# CC1101-CC1190.net
KiCad netlist of a schematic drawn in Altium Designer
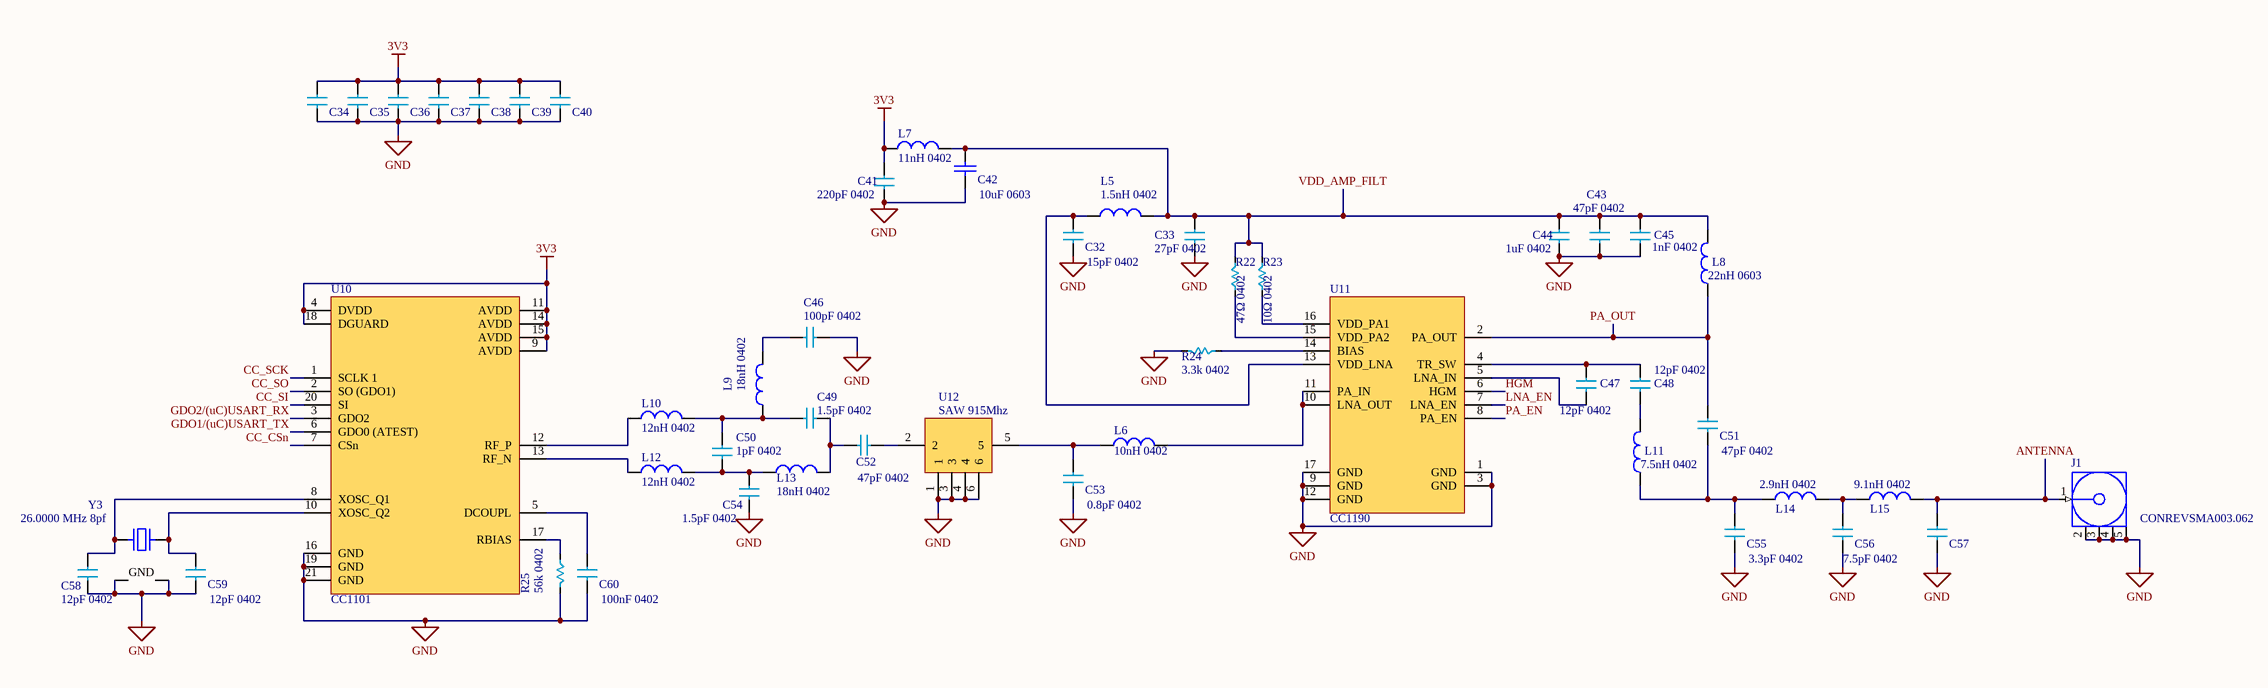
[diagram p0: CC1101-CC1190.SchDoc]

(export (version "E")
  (design (tool "Eeschema 10.0.6"))
  (components
    (comp (ref "C32") (value "15pF 0402") (footprint "C0402") (libsource (lib "RLC") (part "C0402-15pF")))
    (comp (ref "C33") (value "27pF 0402") (footprint "C0402") (libsource (lib "RLC") (part "C0402-27pF")))
    (comp (ref "C34") (value "100nF 0402") (footprint "C0402") (libsource (lib "RLC") (part "C0402-100nF")))
    (comp (ref "C35") (value "100nF 0402") (footprint "C0402") (libsource (lib "RLC") (part "C0402-100nF")))
    (comp (ref "C36") (value "100nF 0402") (footprint "C0402") (libsource (lib "RLC") (part "C0402-100nF")))
    (comp (ref "C37") (value "100nF 0402") (footprint "C0402") (libsource (lib "RLC") (part "C0402-100nF")))
    (comp (ref "C38") (value "100nF 0402") (footprint "C0402") (libsource (lib "RLC") (part "C0402-100nF")))
    (comp (ref "C39") (value "100nF 0402") (footprint "C0402") (libsource (lib "RLC") (part "C0402-100nF")))
    (comp (ref "C40") (value "100nF 0402") (footprint "C0402") (libsource (lib "RLC") (part "C0402-100nF")))
    (comp (ref "C41") (value "220pF 0402") (footprint "C0402") (libsource (lib "RLC") (part "C0402-220pF")))
    (comp (ref "C42") (value "10uF 0603") (footprint "C0603") (libsource (lib "RLC") (part "C-10.0uF-0603")))
    (comp (ref "C43") (value "47pF 0402") (footprint "C0402") (libsource (lib "RLC") (part "C0402-47pF")))
    (comp (ref "C44") (value "1uF 0402") (footprint "C0402") (libsource (lib "RLC") (part "C0402-1uF")))
    (comp (ref "C45") (value "1nF 0402") (footprint "C0402") (libsource (lib "RLC") (part "C0402-1nF")))
    (comp (ref "C46") (value "100pF 0402") (footprint "C0402") (libsource (lib "RLC") (part "C0402-100pF")))
    (comp (ref "C47") (value "12pF 0402") (footprint "C0402") (libsource (lib "RLC") (part "C0402-12pF")))
    (comp (ref "C48") (value "12pF 0402") (footprint "C0402") (libsource (lib "RLC") (part "C0402-12pF")))
    (comp (ref "C49") (value "1.5pF 0402") (footprint "C0402") (libsource (lib "RLC") (part "C0402-1.5pF")))
    (comp (ref "C50") (value "1pF 0402") (footprint "C0402") (libsource (lib "RLC") (part "C0402-1pF")))
    (comp (ref "C51") (value "47pF 0402") (footprint "C0402") (libsource (lib "RLC") (part "C0402-47pF")))
    (comp (ref "C52") (value "47pF 0402") (footprint "C0402") (libsource (lib "RLC") (part "C0402-47pF")))
    (comp (ref "C53") (value "0.8pF 0402") (footprint "C0402") (libsource (lib "RLC") (part "C0402-0.8pF")))
    (comp (ref "C54") (value "1.5pF 0402") (footprint "C0402") (libsource (lib "RLC") (part "C0402-1.5pF")))
    (comp (ref "C55") (value "3.3pF 0402") (footprint "C0402") (libsource (lib "RLC") (part "C0402-3.3pF")))
    (comp (ref "C56") (value "7.5pF 0402") (footprint "C0402") (libsource (lib "RLC") (part "C0402-7.5pF")))
    (comp (ref "C57")
      (value "Placeholder")
      (footprint "C0402")
      (description "Placeholder Cap")
      (libsource (lib "RLC") (part "C0402-?"))
    )
    (comp (ref "C58") (value "12pF 0402") (footprint "C0402") (libsource (lib "RLC") (part "C0402-12pF")))
    (comp (ref "C59") (value "12pF 0402") (footprint "C0402") (libsource (lib "RLC") (part "C0402-12pF")))
    (comp (ref "C60") (value "100nF 0402") (footprint "C0402") (libsource (lib "RLC") (part "C0402-100nF")))
    (comp (ref "J1")
      (value "CONREVSMA003.062")
      (footprint "CON-SMA-EDGE062")
      (description "RP-SMA Female Edge Mount Connector for 0.062\" Thick Board")
      (libsource (lib "robot-cortex") (part "CONREVSMA003.062"))
    )
    (comp (ref "L5") (value "1.5nH 0402") (footprint "L0402") (libsource (lib "RLC") (part "L0402-1.5nH")))
    (comp (ref "L6") (value "10nH 0402") (footprint "L0402") (libsource (lib "RLC") (part "L0402-10nH")))
    (comp (ref "L7") (value "11nH 0402") (footprint "L0402") (libsource (lib "RLC") (part "L0402-11nH")))
    (comp (ref "L8") (value "22nH 0603") (footprint "L0603") (libsource (lib "RLC") (part "L0603-22nH")))
    (comp (ref "L9") (value "18nH 0402") (footprint "L0402") (libsource (lib "RLC") (part "L0402-18nH")))
    (comp (ref "L10") (value "12nH 0402") (footprint "L0402") (libsource (lib "RLC") (part "L0402-12nH")))
    (comp (ref "L11") (value "7.5nH 0402") (footprint "L0402") (libsource (lib "RLC") (part "L0402-7.5nH")))
    (comp (ref "L12") (value "12nH 0402") (footprint "L0402") (libsource (lib "RLC") (part "L0402-12nH")))
    (comp (ref "L13") (value "18nH 0402") (footprint "L0402") (libsource (lib "RLC") (part "L0402-18nH")))
    (comp (ref "L14") (value "2.9nH 0402") (footprint "L0402") (libsource (lib "RLC") (part "L0402-2.9")))
    (comp (ref "L15") (value "9.1nH 0402") (footprint "L0402") (libsource (lib "RLC") (part "L0402-9.1nH")))
    (comp (ref "R22") (value "47Ω 0402") (footprint "R0402") (libsource (lib "RLC") (part "R-47-0402")))
    (comp (ref "R23") (value "10Ω 0402") (footprint "R0402") (libsource (lib "RLC") (part "R-10-0402")))
    (comp (ref "R24") (value "3.3k 0402") (footprint "R0402") (libsource (lib "RLC") (part "R-3.3k-0402")))
    (comp (ref "R25") (value "56k 0402") (footprint "R0402") (libsource (lib "RLC") (part "R-56k-0402")))
    (comp (ref "U10")
      (value "CC1101")
      (footprint "QFN20-TI")
      (description "RF Transceiver IC")
      (libsource (lib "robot-cortex") (part "CC1101"))
    )
    (comp (ref "U11")
      (value "CC1190")
      (footprint "QFN16-TI")
      (description "RF frontend")
      (libsource (lib "robot-cortex") (part "CC1190"))
    )
    (comp (ref "U12")
      (value "SAW 915Mhz")
      (footprint "DCC6C")
      (description "FILTER SAW 915MHZ REMOTE SMD")
      (fields
        (field (name "MANUFACTURER") "TDK EPCOS")
        (field (name "MANUFACTURER PART NUMBER") "B39921B3726U410")
      )
      (libsource (lib "robot-cortex") (part "B39921B3726U410"))
    )
    (comp (ref "Y3")
      (value "26.0000 MHz 8pf")
      (footprint "robot-cortex:NDK NX3225GA")
      (description "Crystal 26MHz 8pF 4-Pin SMD")
      (fields
        (field (name "MANUFACTURER") "NDK")
        (field (name "MANUFACTURER PART NUMBER") "NX3225SA-26.000M-STD-CSR-3")
      )
      (libsource (lib "robot-cortex") (part "NX3225SA-26.000M-STD-CSR-3"))
    )
  )
  (nets
    (net (code "1") (name "/ANTENNA") (class "Default")
      (node (ref "C57") (pin "1") (pinfunction "1_1") (pintype "passive"))
      (node (ref "J1") (pin "1") (pinfunction "Signal_1") (pintype "input"))
      (node (ref "L15") (pin "2") (pinfunction "2_2") (pintype "passive"))
    )
    (net (code "2") (name "/CC_CSn") (class "Default")
      (node (ref "U10") (pin "7") (pinfunction "CSn_7") (pintype "passive"))
    )
    (net (code "3") (name "/CC_SCK") (class "Default")
      (node (ref "U10") (pin "1") (pinfunction "SCLK_1_1") (pintype "passive"))
    )
    (net (code "4") (name "/CC_SI") (class "Default")
      (node (ref "U10") (pin "20") (pinfunction "SI_20") (pintype "passive"))
    )
    (net (code "5") (name "/CC_SO") (class "Default")
      (node (ref "U10") (pin "2") (pinfunction "SO_(GDO1)_2") (pintype "passive"))
    )
    (net (code "6") (name "/GDO1{slash}(uC)USART_TX") (class "Default")
      (node (ref "U10") (pin "6") (pinfunction "GDO0_(ATEST)_6") (pintype "passive"))
    )
    (net (code "7") (name "/GDO2{slash}(uC)USART_RX") (class "Default")
      (node (ref "U10") (pin "3") (pinfunction "GDO2_3") (pintype "passive"))
    )
    (net (code "8") (name "/HGM") (class "Default")
      (node (ref "U11") (pin "6") (pinfunction "HGM_6") (pintype "passive"))
    )
    (net (code "9") (name "/LNA_EN") (class "Default")
      (node (ref "U11") (pin "7") (pinfunction "LNA_EN_7") (pintype "passive"))
    )
    (net (code "10") (name "/PA_EN") (class "Default")
      (node (ref "U11") (pin "8") (pinfunction "PA_EN_8") (pintype "passive"))
    )
    (net (code "11") (name "/PA_OUT") (class "Default")
      (node (ref "C51") (pin "1") (pinfunction "1_1") (pintype "passive"))
      (node (ref "L8") (pin "1") (pinfunction "1_1") (pintype "passive"))
      (node (ref "U11") (pin "2") (pinfunction "PA_OUT_2") (pintype "passive"))
    )
    (net (code "12") (name "/VDD_AMP_FILT") (class "Default")
      (node (ref "C33") (pin "1") (pinfunction "1_1") (pintype "passive"))
      (node (ref "C42") (pin "2") (pinfunction "2_2") (pintype "passive"))
      (node (ref "C43") (pin "1") (pinfunction "1_1") (pintype "passive"))
      (node (ref "C44") (pin "1") (pinfunction "1_1") (pintype "passive"))
      (node (ref "C45") (pin "1") (pinfunction "1_1") (pintype "passive"))
      (node (ref "L5") (pin "2") (pinfunction "2_2") (pintype "passive"))
      (node (ref "L7") (pin "2") (pinfunction "2_2") (pintype "passive"))
      (node (ref "L8") (pin "2") (pinfunction "2_2") (pintype "passive"))
      (node (ref "R22") (pin "1") (pinfunction "1_1") (pintype "passive"))
      (node (ref "R23") (pin "1") (pinfunction "1_1") (pintype "passive"))
    )
    (net (code "13") (name "3V3") (class "Default")
      (node (ref "C34") (pin "2") (pinfunction "2_2") (pintype "passive"))
      (node (ref "C35") (pin "2") (pinfunction "2_2") (pintype "passive"))
      (node (ref "C36") (pin "2") (pinfunction "2_2") (pintype "passive"))
      (node (ref "C37") (pin "2") (pinfunction "2_2") (pintype "passive"))
      (node (ref "C38") (pin "2") (pinfunction "2_2") (pintype "passive"))
      (node (ref "C39") (pin "2") (pinfunction "2_2") (pintype "passive"))
      (node (ref "C40") (pin "2") (pinfunction "2_2") (pintype "passive"))
      (node (ref "C41") (pin "1") (pinfunction "1_1") (pintype "passive"))
      (node (ref "L7") (pin "1") (pinfunction "1_1") (pintype "passive"))
      (node (ref "U10") (pin "11") (pinfunction "AVDD_11") (pintype "passive"))
      (node (ref "U10") (pin "14") (pinfunction "AVDD_14") (pintype "passive"))
      (node (ref "U10") (pin "15") (pinfunction "AVDD_15") (pintype "passive"))
      (node (ref "U10") (pin "18") (pinfunction "DGUARD_18") (pintype "passive"))
      (node (ref "U10") (pin "4") (pinfunction "DVDD_4") (pintype "passive"))
      (node (ref "U10") (pin "9") (pinfunction "AVDD_9") (pintype "passive"))
    )
    (net (code "14") (name "GND") (class "Default")
      (node (ref "C32") (pin "2") (pinfunction "2_2") (pintype "passive"))
      (node (ref "C33") (pin "2") (pinfunction "2_2") (pintype "passive"))
      (node (ref "C34") (pin "1") (pinfunction "1_1") (pintype "passive"))
      (node (ref "C35") (pin "1") (pinfunction "1_1") (pintype "passive"))
      (node (ref "C36") (pin "1") (pinfunction "1_1") (pintype "passive"))
      (node (ref "C37") (pin "1") (pinfunction "1_1") (pintype "passive"))
      (node (ref "C38") (pin "1") (pinfunction "1_1") (pintype "passive"))
      (node (ref "C39") (pin "1") (pinfunction "1_1") (pintype "passive"))
      (node (ref "C40") (pin "1") (pinfunction "1_1") (pintype "passive"))
      (node (ref "C41") (pin "2") (pinfunction "2_2") (pintype "passive"))
      (node (ref "C42") (pin "1") (pinfunction "1_1") (pintype "passive"))
      (node (ref "C43") (pin "2") (pinfunction "2_2") (pintype "passive"))
      (node (ref "C44") (pin "2") (pinfunction "2_2") (pintype "passive"))
      (node (ref "C45") (pin "2") (pinfunction "2_2") (pintype "passive"))
      (node (ref "C46") (pin "1") (pinfunction "1_1") (pintype "passive"))
      (node (ref "C53") (pin "2") (pinfunction "2_2") (pintype "passive"))
      (node (ref "C54") (pin "1") (pinfunction "1_1") (pintype "passive"))
      (node (ref "C55") (pin "2") (pinfunction "2_2") (pintype "passive"))
      (node (ref "C56") (pin "2") (pinfunction "2_2") (pintype "passive"))
      (node (ref "C57") (pin "2") (pinfunction "2_2") (pintype "passive"))
      (node (ref "C58") (pin "1") (pinfunction "1_1") (pintype "passive"))
      (node (ref "C59") (pin "1") (pinfunction "1_1") (pintype "passive"))
      (node (ref "C60") (pin "1") (pinfunction "1_1") (pintype "passive"))
      (node (ref "J1") (pin "2") (pinfunction "GND_2") (pintype "power_in"))
      (node (ref "J1") (pin "3") (pinfunction "GND_3") (pintype "power_in"))
      (node (ref "J1") (pin "4") (pinfunction "GND_4") (pintype "power_in"))
      (node (ref "J1") (pin "5") (pinfunction "GND_5") (pintype "power_in"))
      (node (ref "R24") (pin "1") (pinfunction "1_1") (pintype "passive"))
      (node (ref "R25") (pin "1") (pinfunction "1_1") (pintype "passive"))
      (node (ref "U10") (pin "16") (pinfunction "GND_16") (pintype "passive"))
      (node (ref "U10") (pin "19") (pinfunction "GND_19") (pintype "passive"))
      (node (ref "U10") (pin "21") (pinfunction "GND_21") (pintype "passive"))
      (node (ref "U11") (pin "1") (pinfunction "GND_1") (pintype "passive"))
      (node (ref "U11") (pin "12") (pinfunction "GND_12") (pintype "passive"))
      (node (ref "U11") (pin "17") (pinfunction "GND_17") (pintype "passive"))
      (node (ref "U11") (pin "3") (pinfunction "GND_3") (pintype "passive"))
      (node (ref "U11") (pin "9") (pinfunction "GND_9") (pintype "passive"))
      (node (ref "U12") (pin "1") (pinfunction "1_1") (pintype "passive"))
      (node (ref "U12") (pin "3") (pinfunction "3_3") (pintype "passive"))
      (node (ref "U12") (pin "4") (pinfunction "4_4") (pintype "passive"))
      (node (ref "U12") (pin "6") (pinfunction "6_6") (pintype "passive"))
      (node (ref "Y3") (pin "2") (pinfunction "GND_2") (pintype "passive"))
      (node (ref "Y3") (pin "4") (pinfunction "GND_4") (pintype "passive"))
    )
    (net (code "15") (name "Net-(C46-Pad2)") (class "Default")
      (node (ref "C46") (pin "2") (pinfunction "2_2") (pintype "passive"))
      (node (ref "L9") (pin "2") (pinfunction "2_2") (pintype "passive"))
    )
    (net (code "16") (name "Net-(C48-Pad2)") (class "Default")
      (node (ref "C48") (pin "2") (pinfunction "2_2") (pintype "passive"))
      (node (ref "L11") (pin "2") (pinfunction "2_2") (pintype "passive"))
    )
    (net (code "17") (name "Net-(C49-Pad1)") (class "Default")
      (node (ref "C49") (pin "1") (pinfunction "1_1") (pintype "passive"))
      (node (ref "C50") (pin "2") (pinfunction "2_2") (pintype "passive"))
      (node (ref "L10") (pin "2") (pinfunction "2_2") (pintype "passive"))
      (node (ref "L9") (pin "1") (pinfunction "1_1") (pintype "passive"))
    )
    (net (code "18") (name "Net-(C49-Pad2)") (class "Default")
      (node (ref "C49") (pin "2") (pinfunction "2_2") (pintype "passive"))
      (node (ref "C52") (pin "1") (pinfunction "1_1") (pintype "passive"))
      (node (ref "L13") (pin "2") (pinfunction "2_2") (pintype "passive"))
    )
    (net (code "19") (name "Net-(C50-Pad1)") (class "Default")
      (node (ref "C50") (pin "1") (pinfunction "1_1") (pintype "passive"))
      (node (ref "C54") (pin "2") (pinfunction "2_2") (pintype "passive"))
      (node (ref "L12") (pin "2") (pinfunction "2_2") (pintype "passive"))
      (node (ref "L13") (pin "1") (pinfunction "1_1") (pintype "passive"))
    )
    (net (code "20") (name "Net-(C51-Pad2)") (class "Default")
      (node (ref "C51") (pin "2") (pinfunction "2_2") (pintype "passive"))
      (node (ref "C55") (pin "1") (pinfunction "1_1") (pintype "passive"))
      (node (ref "L11") (pin "1") (pinfunction "1_1") (pintype "passive"))
      (node (ref "L14") (pin "1") (pinfunction "1_1") (pintype "passive"))
    )
    (net (code "21") (name "Net-(C52-Pad2)") (class "Default")
      (node (ref "C52") (pin "2") (pinfunction "2_2") (pintype "passive"))
      (node (ref "U12") (pin "2") (pinfunction "2_2") (pintype "passive"))
    )
    (net (code "22") (name "Net-(C53-Pad1)") (class "Default")
      (node (ref "C53") (pin "1") (pinfunction "1_1") (pintype "passive"))
      (node (ref "L6") (pin "1") (pinfunction "1_1") (pintype "passive"))
      (node (ref "U12") (pin "5") (pinfunction "5_5") (pintype "passive"))
    )
    (net (code "23") (name "Net-(C56-Pad1)") (class "Default")
      (node (ref "C56") (pin "1") (pinfunction "1_1") (pintype "passive"))
      (node (ref "L14") (pin "2") (pinfunction "2_2") (pintype "passive"))
      (node (ref "L15") (pin "1") (pinfunction "1_1") (pintype "passive"))
    )
    (net (code "24") (name "Net-(U10-DCOUPL)") (class "Default")
      (node (ref "C60") (pin "2") (pinfunction "2_2") (pintype "passive"))
      (node (ref "U10") (pin "5") (pinfunction "DCOUPL_5") (pintype "passive"))
    )
    (net (code "25") (name "Net-(U10-RBIAS)") (class "Default")
      (node (ref "R25") (pin "2") (pinfunction "2_2") (pintype "passive"))
      (node (ref "U10") (pin "17") (pinfunction "RBIAS_17") (pintype "passive"))
    )
    (net (code "26") (name "Net-(U10-RF_N)") (class "Default")
      (node (ref "L12") (pin "1") (pinfunction "1_1") (pintype "passive"))
      (node (ref "U10") (pin "13") (pinfunction "RF_N_13") (pintype "passive"))
    )
    (net (code "27") (name "Net-(U10-RF_P)") (class "Default")
      (node (ref "L10") (pin "1") (pinfunction "1_1") (pintype "passive"))
      (node (ref "U10") (pin "12") (pinfunction "RF_P_12") (pintype "passive"))
    )
    (net (code "28") (name "Net-(U10-XOSC_Q1)") (class "Default")
      (node (ref "C58") (pin "2") (pinfunction "2_2") (pintype "passive"))
      (node (ref "U10") (pin "8") (pinfunction "XOSC_Q1_8") (pintype "passive"))
      (node (ref "Y3") (pin "1") (pinfunction "1_1") (pintype "passive"))
    )
    (net (code "29") (name "Net-(U10-XOSC_Q2)") (class "Default")
      (node (ref "C59") (pin "2") (pinfunction "2_2") (pintype "passive"))
      (node (ref "U10") (pin "10") (pinfunction "XOSC_Q2_10") (pintype "passive"))
      (node (ref "Y3") (pin "3") (pinfunction "3_3") (pintype "passive"))
    )
    (net (code "30") (name "Net-(U11-BIAS)") (class "Default")
      (node (ref "R24") (pin "2") (pinfunction "2_2") (pintype "passive"))
      (node (ref "U11") (pin "14") (pinfunction "BIAS_14") (pintype "passive"))
    )
    (net (code "31") (name "Net-(U11-LNA_IN)") (class "Default")
      (node (ref "C47") (pin "2") (pinfunction "2_2") (pintype "passive"))
      (node (ref "U11") (pin "5") (pinfunction "LNA_IN_5") (pintype "passive"))
    )
    (net (code "32") (name "Net-(U11-LNA_OUT)") (class "Default")
      (node (ref "L6") (pin "2") (pinfunction "2_2") (pintype "passive"))
      (node (ref "U11") (pin "10") (pinfunction "LNA_OUT_10") (pintype "passive"))
      (node (ref "U11") (pin "11") (pinfunction "PA_IN_11") (pintype "passive"))
    )
    (net (code "33") (name "Net-(U11-TR_SW)") (class "Default")
      (node (ref "C47") (pin "1") (pinfunction "1_1") (pintype "passive"))
      (node (ref "C48") (pin "1") (pinfunction "1_1") (pintype "passive"))
      (node (ref "U11") (pin "4") (pinfunction "TR_SW_4") (pintype "passive"))
    )
    (net (code "34") (name "Net-(U11-VDD_LNA)") (class "Default")
      (node (ref "C32") (pin "1") (pinfunction "1_1") (pintype "passive"))
      (node (ref "L5") (pin "1") (pinfunction "1_1") (pintype "passive"))
      (node (ref "U11") (pin "13") (pinfunction "VDD_LNA_13") (pintype "passive"))
    )
    (net (code "35") (name "Net-(U11-VDD_PA1)") (class "Default")
      (node (ref "R23") (pin "2") (pinfunction "2_2") (pintype "passive"))
      (node (ref "U11") (pin "16") (pinfunction "VDD_PA1_16") (pintype "passive"))
    )
    (net (code "36") (name "Net-(U11-VDD_PA2)") (class "Default")
      (node (ref "R22") (pin "2") (pinfunction "2_2") (pintype "passive"))
      (node (ref "U11") (pin "15") (pinfunction "VDD_PA2_15") (pintype "passive"))
    )
  )
)
